# capstone_electrical_circuit_rev2.net
KiCad netlist of a schematic drawn in EAGLE
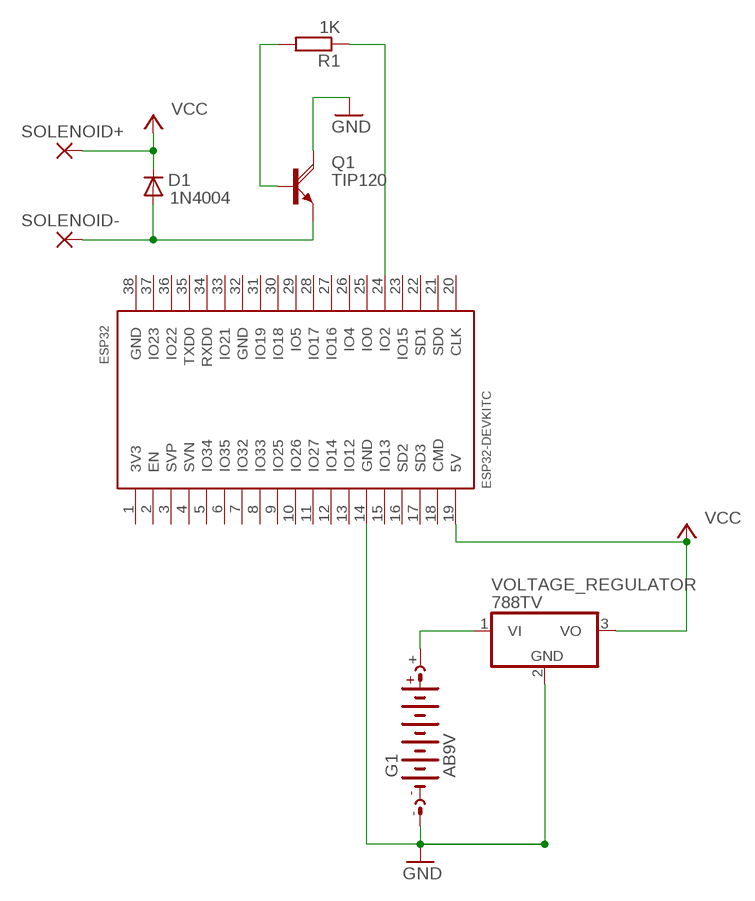
[diagram p0: schematic, sheet 1]

(export (version "E")
  (design (tool "Eeschema 10.0.6"))
  (components
    (comp (ref "D1")
      (value "1N4004")
      (footprint "eagle-import:DO41-10")
      (libsource (lib "eagle-import") (part "1N4004"))
    )
    (comp (ref "ESP32")
      (value "ESP32DEVKITC")
      (footprint "eagle-import:ESP32-DEVKITC")
      (libsource (lib "eagle-import") (part "ESP32DEVKITC"))
    )
    (comp (ref "G1")
      (value "AB9V")
      (footprint "eagle-import:AB9V")
      (libsource (lib "eagle-import") (part "AB9V"))
    )
    (comp (ref "Q1")
      (value "TIP120")
      (footprint "eagle-import:TO220AH")
      (libsource (lib "eagle-import") (part "TIP120"))
    )
    (comp (ref "R1")
      (value "1K")
      (footprint "eagle-import:0207_10")
      (libsource (lib "eagle-import") (part "R-EU_0207/10"))
    )
    (comp (ref "SOLENOID+")
      (value "WIREPAD2,54/1,0")
      (footprint "eagle-import:2,54_1,0")
      (libsource (lib "eagle-import") (part "WIREPAD2,54/1,0"))
    )
    (comp (ref "SOLENOID-")
      (value "WIREPAD2,54/1,0")
      (footprint "eagle-import:2,54_1,0")
      (libsource (lib "eagle-import") (part "WIREPAD2,54/1,0"))
    )
    (comp (ref "VOLTAGE_REGULATOR")
      (value "788TV")
      (footprint "eagle-import:TO220V")
      (libsource (lib "eagle-import") (part "78TV8"))
    )
  )
  (nets
    (net (code "1") (name "GND") (class "Default")
      (node (ref "ESP32") (pin "14") (pinfunction "GND_14") (pintype "bidirectional"))
      (node (ref "G1") (pin "-") (pinfunction "-_-") (pintype "passive"))
      (node (ref "Q1") (pin "C") (pinfunction "C_C") (pintype "passive"))
      (node (ref "VOLTAGE_REGULATOR") (pin "2") (pinfunction "GND_2") (pintype "passive"))
    )
    (net (code "2") (name "Net-(ESP32-IO2)") (class "Default")
      (node (ref "ESP32") (pin "24") (pinfunction "IO2_24") (pintype "bidirectional"))
      (node (ref "R1") (pin "1") (pinfunction "1_1") (pintype "passive"))
    )
    (net (code "3") (name "Net-(Q1-PadB)") (class "Default")
      (node (ref "Q1") (pin "B") (pinfunction "B_B") (pintype "passive"))
      (node (ref "R1") (pin "2") (pinfunction "2_2") (pintype "passive"))
    )
    (net (code "4") (name "Net-(SOLENOID--P)") (class "Default")
      (node (ref "D1") (pin "A") (pinfunction "A_A") (pintype "passive"))
      (node (ref "Q1") (pin "E") (pinfunction "E_E") (pintype "passive"))
      (node (ref "SOLENOID-") (pin "1") (pinfunction "P_1") (pintype "passive"))
    )
    (net (code "5") (name "Net-(VOLTAGE_REGULATOR-VI)") (class "Default")
      (node (ref "G1") (pin "+") (pinfunction "+_+") (pintype "passive"))
      (node (ref "VOLTAGE_REGULATOR") (pin "1") (pinfunction "VI_1") (pintype "input"))
    )
    (net (code "6") (name "VCC") (class "Default")
      (node (ref "D1") (pin "C") (pinfunction "C_C") (pintype "passive"))
      (node (ref "ESP32") (pin "19") (pinfunction "5V_19") (pintype "bidirectional"))
      (node (ref "SOLENOID+") (pin "1") (pinfunction "P_1") (pintype "passive"))
      (node (ref "VOLTAGE_REGULATOR") (pin "3") (pinfunction "VO_3") (pintype "passive"))
    )
    (net (code "7") (name "unconnected-(ESP32-3V3-Pad1)") (class "Default")
      (node (ref "ESP32") (pin "1") (pinfunction "3V3_1") (pintype "bidirectional"))
    )
    (net (code "8") (name "unconnected-(ESP32-CLK-Pad20)") (class "Default")
      (node (ref "ESP32") (pin "20") (pinfunction "CLK_20") (pintype "bidirectional"))
    )
    (net (code "9") (name "unconnected-(ESP32-CMD-Pad18)") (class "Default")
      (node (ref "ESP32") (pin "18") (pinfunction "CMD_18") (pintype "bidirectional"))
    )
    (net (code "10") (name "unconnected-(ESP32-EN-Pad2)") (class "Default")
      (node (ref "ESP32") (pin "2") (pinfunction "EN_2") (pintype "bidirectional"))
    )
    (net (code "11") (name "unconnected-(ESP32-GND-Pad32)") (class "Default")
      (node (ref "ESP32") (pin "32") (pinfunction "GND_32") (pintype "bidirectional"))
    )
    (net (code "12") (name "unconnected-(ESP32-GND-Pad38)") (class "Default")
      (node (ref "ESP32") (pin "38") (pinfunction "GND_38") (pintype "bidirectional"))
    )
    (net (code "13") (name "unconnected-(ESP32-IO0-Pad25)") (class "Default")
      (node (ref "ESP32") (pin "25") (pinfunction "IO0_25") (pintype "bidirectional"))
    )
    (net (code "14") (name "unconnected-(ESP32-IO4-Pad26)") (class "Default")
      (node (ref "ESP32") (pin "26") (pinfunction "IO4_26") (pintype "bidirectional"))
    )
    (net (code "15") (name "unconnected-(ESP32-IO5-Pad29)") (class "Default")
      (node (ref "ESP32") (pin "29") (pinfunction "IO5_29") (pintype "bidirectional"))
    )
    (net (code "16") (name "unconnected-(ESP32-IO12-Pad13)") (class "Default")
      (node (ref "ESP32") (pin "13") (pinfunction "IO12_13") (pintype "bidirectional"))
    )
    (net (code "17") (name "unconnected-(ESP32-IO13-Pad15)") (class "Default")
      (node (ref "ESP32") (pin "15") (pinfunction "IO13_15") (pintype "bidirectional"))
    )
    (net (code "18") (name "unconnected-(ESP32-IO14-Pad12)") (class "Default")
      (node (ref "ESP32") (pin "12") (pinfunction "IO14_12") (pintype "bidirectional"))
    )
    (net (code "19") (name "unconnected-(ESP32-IO15-Pad23)") (class "Default")
      (node (ref "ESP32") (pin "23") (pinfunction "IO15_23") (pintype "bidirectional"))
    )
    (net (code "20") (name "unconnected-(ESP32-IO16-Pad27)") (class "Default")
      (node (ref "ESP32") (pin "27") (pinfunction "IO16_27") (pintype "bidirectional"))
    )
    (net (code "21") (name "unconnected-(ESP32-IO17-Pad28)") (class "Default")
      (node (ref "ESP32") (pin "28") (pinfunction "IO17_28") (pintype "bidirectional"))
    )
    (net (code "22") (name "unconnected-(ESP32-IO18-Pad30)") (class "Default")
      (node (ref "ESP32") (pin "30") (pinfunction "IO18_30") (pintype "bidirectional"))
    )
    (net (code "23") (name "unconnected-(ESP32-IO19-Pad31)") (class "Default")
      (node (ref "ESP32") (pin "31") (pinfunction "IO19_31") (pintype "bidirectional"))
    )
    (net (code "24") (name "unconnected-(ESP32-IO21-Pad33)") (class "Default")
      (node (ref "ESP32") (pin "33") (pinfunction "IO21_33") (pintype "bidirectional"))
    )
    (net (code "25") (name "unconnected-(ESP32-IO22-Pad36)") (class "Default")
      (node (ref "ESP32") (pin "36") (pinfunction "IO22_36") (pintype "bidirectional"))
    )
    (net (code "26") (name "unconnected-(ESP32-IO23-Pad37)") (class "Default")
      (node (ref "ESP32") (pin "37") (pinfunction "IO23_37") (pintype "bidirectional"))
    )
    (net (code "27") (name "unconnected-(ESP32-IO25-Pad9)") (class "Default")
      (node (ref "ESP32") (pin "9") (pinfunction "IO25_9") (pintype "bidirectional"))
    )
    (net (code "28") (name "unconnected-(ESP32-IO26-Pad10)") (class "Default")
      (node (ref "ESP32") (pin "10") (pinfunction "IO26_10") (pintype "bidirectional"))
    )
    (net (code "29") (name "unconnected-(ESP32-IO27-Pad11)") (class "Default")
      (node (ref "ESP32") (pin "11") (pinfunction "IO27_11") (pintype "bidirectional"))
    )
    (net (code "30") (name "unconnected-(ESP32-IO32-Pad7)") (class "Default")
      (node (ref "ESP32") (pin "7") (pinfunction "IO32_7") (pintype "bidirectional"))
    )
    (net (code "31") (name "unconnected-(ESP32-IO33-Pad8)") (class "Default")
      (node (ref "ESP32") (pin "8") (pinfunction "IO33_8") (pintype "bidirectional"))
    )
    (net (code "32") (name "unconnected-(ESP32-IO34-Pad5)") (class "Default")
      (node (ref "ESP32") (pin "5") (pinfunction "IO34_5") (pintype "bidirectional"))
    )
    (net (code "33") (name "unconnected-(ESP32-IO35-Pad6)") (class "Default")
      (node (ref "ESP32") (pin "6") (pinfunction "IO35_6") (pintype "bidirectional"))
    )
    (net (code "34") (name "unconnected-(ESP32-RXD0-Pad34)") (class "Default")
      (node (ref "ESP32") (pin "34") (pinfunction "RXD0_34") (pintype "bidirectional"))
    )
    (net (code "35") (name "unconnected-(ESP32-SD0-Pad21)") (class "Default")
      (node (ref "ESP32") (pin "21") (pinfunction "SD0_21") (pintype "bidirectional"))
    )
    (net (code "36") (name "unconnected-(ESP32-SD1-Pad22)") (class "Default")
      (node (ref "ESP32") (pin "22") (pinfunction "SD1_22") (pintype "bidirectional"))
    )
    (net (code "37") (name "unconnected-(ESP32-SD2-Pad16)") (class "Default")
      (node (ref "ESP32") (pin "16") (pinfunction "SD2_16") (pintype "bidirectional"))
    )
    (net (code "38") (name "unconnected-(ESP32-SD3-Pad17)") (class "Default")
      (node (ref "ESP32") (pin "17") (pinfunction "SD3_17") (pintype "bidirectional"))
    )
    (net (code "39") (name "unconnected-(ESP32-SVN-Pad4)") (class "Default")
      (node (ref "ESP32") (pin "4") (pinfunction "SVN_4") (pintype "bidirectional"))
    )
    (net (code "40") (name "unconnected-(ESP32-SVP-Pad3)") (class "Default")
      (node (ref "ESP32") (pin "3") (pinfunction "SVP_3") (pintype "bidirectional"))
    )
    (net (code "41") (name "unconnected-(ESP32-TXD0-Pad35)") (class "Default")
      (node (ref "ESP32") (pin "35") (pinfunction "TXD0_35") (pintype "bidirectional"))
    )
  )
)
